# recepteur_led.net
KiCad netlist of a schematic drawn in EAGLE
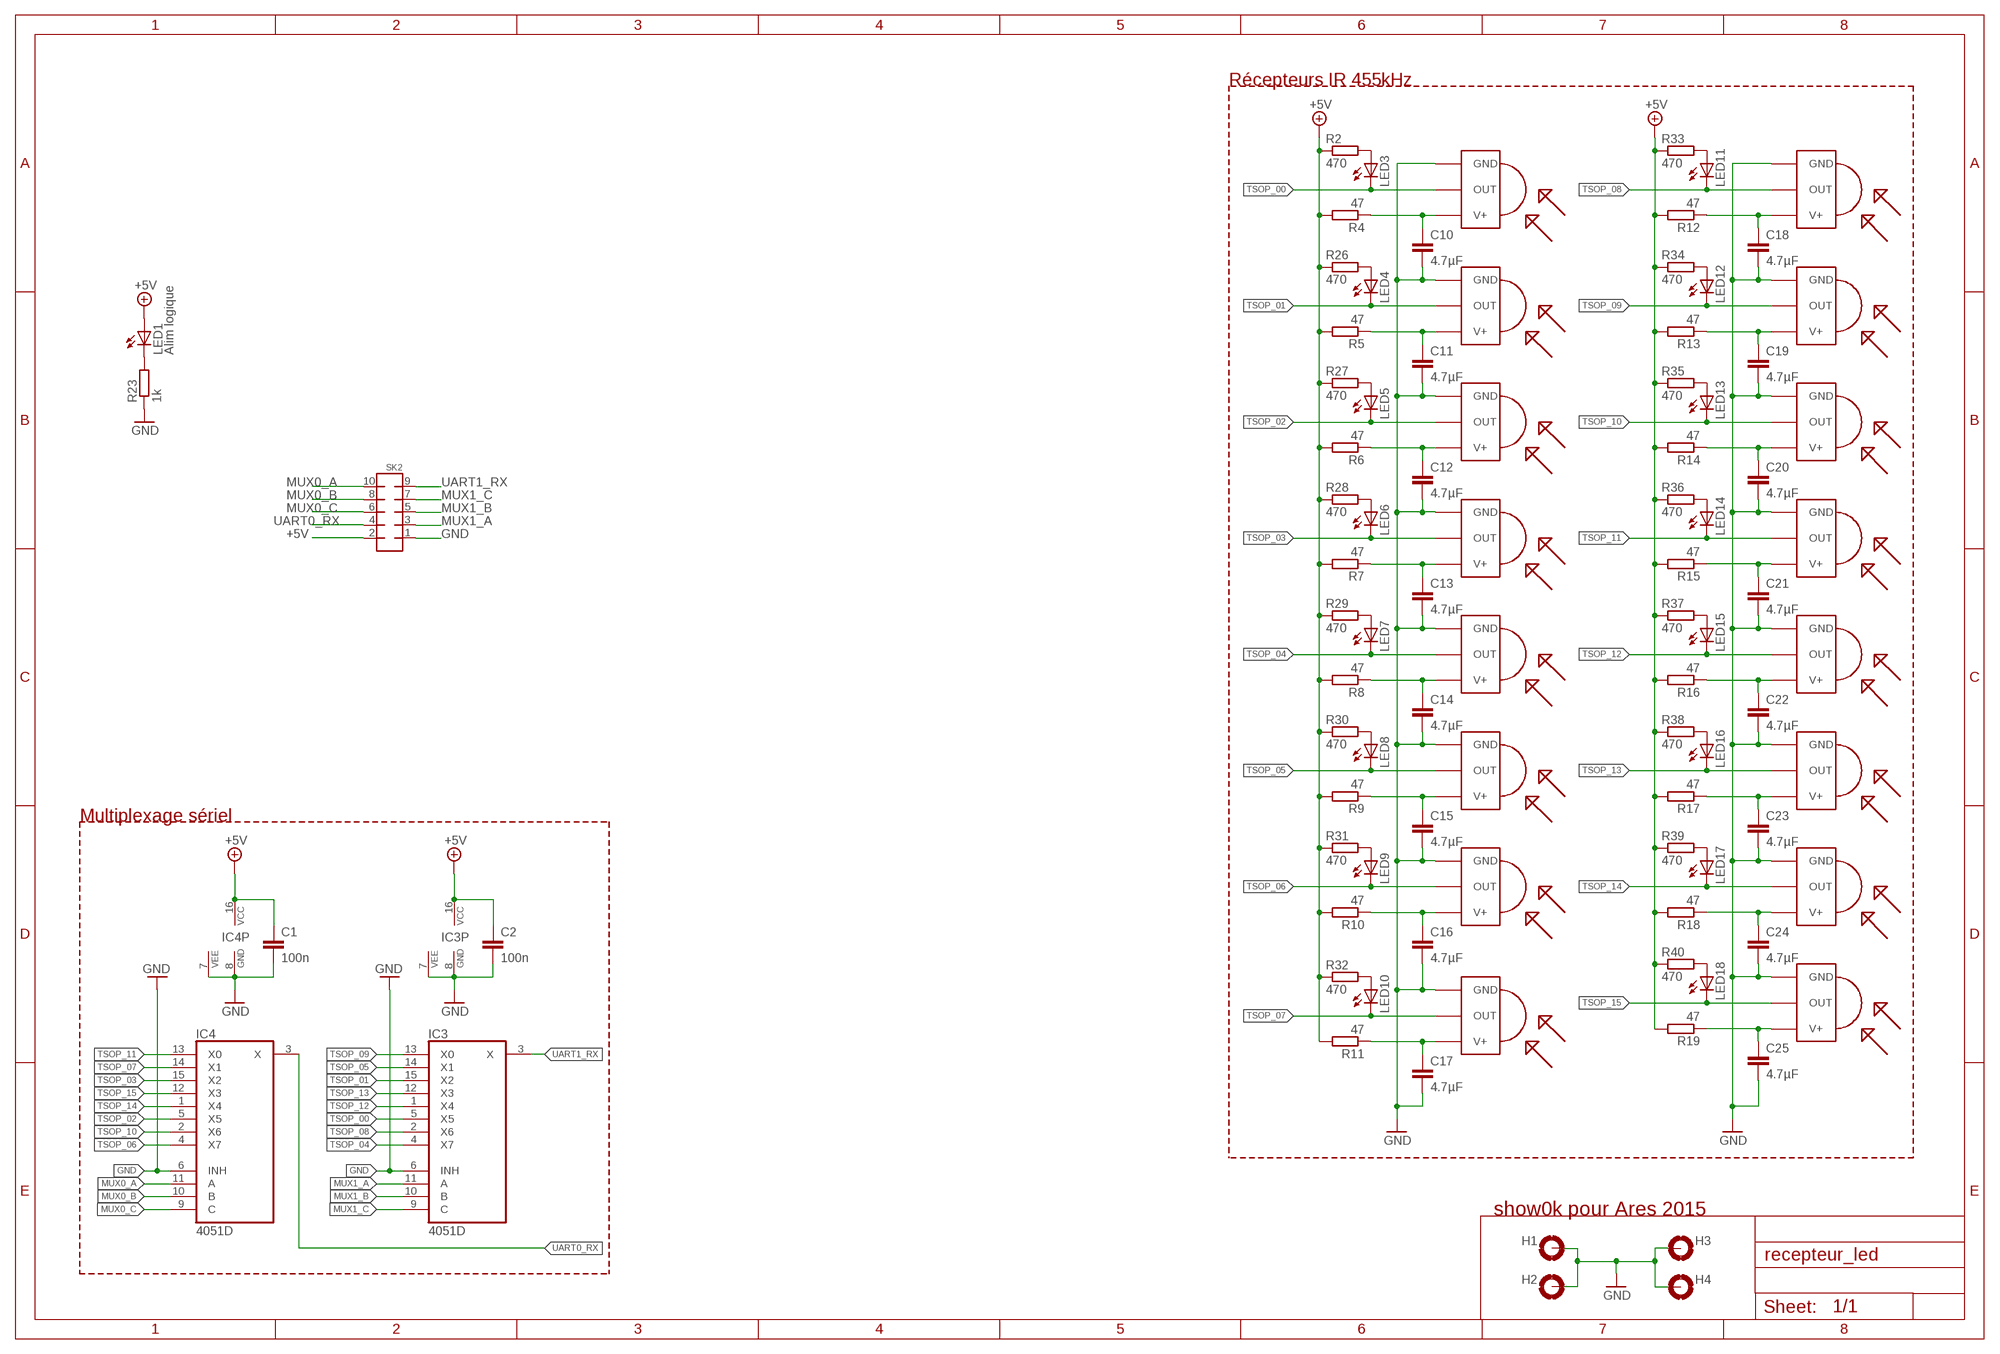
[diagram p0: schematic, sheet 1]

(export (version "E")
  (design (tool "Eeschema 10.0.6"))
  (components
    (comp (ref "C1")
      (value "100n")
      (footprint "eagle-import:C0805")
      (libsource (lib "eagle-import") (part "C-EUC0805"))
    )
    (comp (ref "C2")
      (value "100n")
      (footprint "eagle-import:C0805")
      (libsource (lib "eagle-import") (part "C-EUC0805"))
    )
    (comp (ref "C10")
      (value "4.7µF")
      (footprint "eagle-import:C0805")
      (libsource (lib "eagle-import") (part "C-EUC0805"))
    )
    (comp (ref "C11")
      (value "4.7µF")
      (footprint "eagle-import:C0805")
      (libsource (lib "eagle-import") (part "C-EUC0805"))
    )
    (comp (ref "C12")
      (value "4.7µF")
      (footprint "eagle-import:C0805")
      (libsource (lib "eagle-import") (part "C-EUC0805"))
    )
    (comp (ref "C13")
      (value "4.7µF")
      (footprint "eagle-import:C0805")
      (libsource (lib "eagle-import") (part "C-EUC0805"))
    )
    (comp (ref "C14")
      (value "4.7µF")
      (footprint "eagle-import:C0805")
      (libsource (lib "eagle-import") (part "C-EUC0805"))
    )
    (comp (ref "C15")
      (value "4.7µF")
      (footprint "eagle-import:C0805")
      (libsource (lib "eagle-import") (part "C-EUC0805"))
    )
    (comp (ref "C16")
      (value "4.7µF")
      (footprint "eagle-import:C0805")
      (libsource (lib "eagle-import") (part "C-EUC0805"))
    )
    (comp (ref "C17")
      (value "4.7µF")
      (footprint "eagle-import:C0805")
      (libsource (lib "eagle-import") (part "C-EUC0805"))
    )
    (comp (ref "C18")
      (value "4.7µF")
      (footprint "eagle-import:C0805")
      (libsource (lib "eagle-import") (part "C-EUC0805"))
    )
    (comp (ref "C19")
      (value "4.7µF")
      (footprint "eagle-import:C0805")
      (libsource (lib "eagle-import") (part "C-EUC0805"))
    )
    (comp (ref "C20")
      (value "4.7µF")
      (footprint "eagle-import:C0805")
      (libsource (lib "eagle-import") (part "C-EUC0805"))
    )
    (comp (ref "C21")
      (value "4.7µF")
      (footprint "eagle-import:C0805")
      (libsource (lib "eagle-import") (part "C-EUC0805"))
    )
    (comp (ref "C22")
      (value "4.7µF")
      (footprint "eagle-import:C0805")
      (libsource (lib "eagle-import") (part "C-EUC0805"))
    )
    (comp (ref "C23")
      (value "4.7µF")
      (footprint "eagle-import:C0805")
      (libsource (lib "eagle-import") (part "C-EUC0805"))
    )
    (comp (ref "C24")
      (value "4.7µF")
      (footprint "eagle-import:C0805")
      (libsource (lib "eagle-import") (part "C-EUC0805"))
    )
    (comp (ref "C25")
      (value "4.7µF")
      (footprint "eagle-import:C0805")
      (libsource (lib "eagle-import") (part "C-EUC0805"))
    )
    (comp (ref "H1")
      (value "MOUNT-PAD-ROUND3.0")
      (footprint "eagle-import:3,0-PAD")
      (libsource (lib "eagle-import") (part "MOUNT-PAD-ROUND3.0"))
    )
    (comp (ref "H2")
      (value "MOUNT-PAD-ROUND3.0")
      (footprint "eagle-import:3,0-PAD")
      (libsource (lib "eagle-import") (part "MOUNT-PAD-ROUND3.0"))
    )
    (comp (ref "H3")
      (value "MOUNT-PAD-ROUND3.0")
      (footprint "eagle-import:3,0-PAD")
      (libsource (lib "eagle-import") (part "MOUNT-PAD-ROUND3.0"))
    )
    (comp (ref "H4")
      (value "MOUNT-PAD-ROUND3.0")
      (footprint "eagle-import:3,0-PAD")
      (libsource (lib "eagle-import") (part "MOUNT-PAD-ROUND3.0"))
    )
    (comp (ref "IC3")
      (value "4051D")
      (footprint "eagle-import:SO16")
      (libsource (lib "eagle-import") (part "4051D"))
    )
    (comp (ref "IC4")
      (value "4051D")
      (footprint "eagle-import:SO16")
      (libsource (lib "eagle-import") (part "4051D"))
    )
    (comp (ref "LED1")
      (value "Alim logique")
      (footprint "eagle-import:CHIP-LED0805")
      (libsource (lib "eagle-import") (part "LEDCHIP-LED0805"))
    )
    (comp (ref "LED3")
      (value "LEDCHIP-LED0805")
      (footprint "eagle-import:CHIP-LED0805")
      (libsource (lib "eagle-import") (part "LEDCHIP-LED0805"))
    )
    (comp (ref "LED4")
      (value "LEDCHIP-LED0805")
      (footprint "eagle-import:CHIP-LED0805")
      (libsource (lib "eagle-import") (part "LEDCHIP-LED0805"))
    )
    (comp (ref "LED5")
      (value "LEDCHIP-LED0805")
      (footprint "eagle-import:CHIP-LED0805")
      (libsource (lib "eagle-import") (part "LEDCHIP-LED0805"))
    )
    (comp (ref "LED6")
      (value "LEDCHIP-LED0805")
      (footprint "eagle-import:CHIP-LED0805")
      (libsource (lib "eagle-import") (part "LEDCHIP-LED0805"))
    )
    (comp (ref "LED7")
      (value "LEDCHIP-LED0805")
      (footprint "eagle-import:CHIP-LED0805")
      (libsource (lib "eagle-import") (part "LEDCHIP-LED0805"))
    )
    (comp (ref "LED8")
      (value "LEDCHIP-LED0805")
      (footprint "eagle-import:CHIP-LED0805")
      (libsource (lib "eagle-import") (part "LEDCHIP-LED0805"))
    )
    (comp (ref "LED9")
      (value "LEDCHIP-LED0805")
      (footprint "eagle-import:CHIP-LED0805")
      (libsource (lib "eagle-import") (part "LEDCHIP-LED0805"))
    )
    (comp (ref "LED10")
      (value "LEDCHIP-LED0805")
      (footprint "eagle-import:CHIP-LED0805")
      (libsource (lib "eagle-import") (part "LEDCHIP-LED0805"))
    )
    (comp (ref "LED11")
      (value "LEDCHIP-LED0805")
      (footprint "eagle-import:CHIP-LED0805")
      (libsource (lib "eagle-import") (part "LEDCHIP-LED0805"))
    )
    (comp (ref "LED12")
      (value "LEDCHIP-LED0805")
      (footprint "eagle-import:CHIP-LED0805")
      (libsource (lib "eagle-import") (part "LEDCHIP-LED0805"))
    )
    (comp (ref "LED13")
      (value "LEDCHIP-LED0805")
      (footprint "eagle-import:CHIP-LED0805")
      (libsource (lib "eagle-import") (part "LEDCHIP-LED0805"))
    )
    (comp (ref "LED14")
      (value "LEDCHIP-LED0805")
      (footprint "eagle-import:CHIP-LED0805")
      (libsource (lib "eagle-import") (part "LEDCHIP-LED0805"))
    )
    (comp (ref "LED15")
      (value "LEDCHIP-LED0805")
      (footprint "eagle-import:CHIP-LED0805")
      (libsource (lib "eagle-import") (part "LEDCHIP-LED0805"))
    )
    (comp (ref "LED16")
      (value "LEDCHIP-LED0805")
      (footprint "eagle-import:CHIP-LED0805")
      (libsource (lib "eagle-import") (part "LEDCHIP-LED0805"))
    )
    (comp (ref "LED17")
      (value "LEDCHIP-LED0805")
      (footprint "eagle-import:CHIP-LED0805")
      (libsource (lib "eagle-import") (part "LEDCHIP-LED0805"))
    )
    (comp (ref "LED18")
      (value "LEDCHIP-LED0805")
      (footprint "eagle-import:CHIP-LED0805")
      (libsource (lib "eagle-import") (part "LEDCHIP-LED0805"))
    )
    (comp (ref "R2")
      (value "470")
      (footprint "eagle-import:R0805")
      (libsource (lib "eagle-import") (part "R-EU_R0805"))
    )
    (comp (ref "R4")
      (value "47")
      (footprint "eagle-import:R0805")
      (libsource (lib "eagle-import") (part "R-EU_R0805"))
    )
    (comp (ref "R5")
      (value "47")
      (footprint "eagle-import:R0805")
      (libsource (lib "eagle-import") (part "R-EU_R0805"))
    )
    (comp (ref "R6")
      (value "47")
      (footprint "eagle-import:R0805")
      (libsource (lib "eagle-import") (part "R-EU_R0805"))
    )
    (comp (ref "R7")
      (value "47")
      (footprint "eagle-import:R0805")
      (libsource (lib "eagle-import") (part "R-EU_R0805"))
    )
    (comp (ref "R8")
      (value "47")
      (footprint "eagle-import:R0805")
      (libsource (lib "eagle-import") (part "R-EU_R0805"))
    )
    (comp (ref "R9")
      (value "47")
      (footprint "eagle-import:R0805")
      (libsource (lib "eagle-import") (part "R-EU_R0805"))
    )
    (comp (ref "R10")
      (value "47")
      (footprint "eagle-import:R0805")
      (libsource (lib "eagle-import") (part "R-EU_R0805"))
    )
    (comp (ref "R11")
      (value "47")
      (footprint "eagle-import:R0805")
      (libsource (lib "eagle-import") (part "R-EU_R0805"))
    )
    (comp (ref "R12")
      (value "47")
      (footprint "eagle-import:R0805")
      (libsource (lib "eagle-import") (part "R-EU_R0805"))
    )
    (comp (ref "R13")
      (value "47")
      (footprint "eagle-import:R0805")
      (libsource (lib "eagle-import") (part "R-EU_R0805"))
    )
    (comp (ref "R14")
      (value "47")
      (footprint "eagle-import:R0805")
      (libsource (lib "eagle-import") (part "R-EU_R0805"))
    )
    (comp (ref "R15")
      (value "47")
      (footprint "eagle-import:R0805")
      (libsource (lib "eagle-import") (part "R-EU_R0805"))
    )
    (comp (ref "R16")
      (value "47")
      (footprint "eagle-import:R0805")
      (libsource (lib "eagle-import") (part "R-EU_R0805"))
    )
    (comp (ref "R17")
      (value "47")
      (footprint "eagle-import:R0805")
      (libsource (lib "eagle-import") (part "R-EU_R0805"))
    )
    (comp (ref "R18")
      (value "47")
      (footprint "eagle-import:R0805")
      (libsource (lib "eagle-import") (part "R-EU_R0805"))
    )
    (comp (ref "R19")
      (value "47")
      (footprint "eagle-import:R0805")
      (libsource (lib "eagle-import") (part "R-EU_R0805"))
    )
    (comp (ref "R23")
      (value "1k")
      (footprint "eagle-import:M0805")
      (libsource (lib "eagle-import") (part "R-EU_M0805"))
    )
    (comp (ref "R26")
      (value "470")
      (footprint "eagle-import:R0805")
      (libsource (lib "eagle-import") (part "R-EU_R0805"))
    )
    (comp (ref "R27")
      (value "470")
      (footprint "eagle-import:R0805")
      (libsource (lib "eagle-import") (part "R-EU_R0805"))
    )
    (comp (ref "R28")
      (value "470")
      (footprint "eagle-import:R0805")
      (libsource (lib "eagle-import") (part "R-EU_R0805"))
    )
    (comp (ref "R29")
      (value "470")
      (footprint "eagle-import:R0805")
      (libsource (lib "eagle-import") (part "R-EU_R0805"))
    )
    (comp (ref "R30")
      (value "470")
      (footprint "eagle-import:R0805")
      (libsource (lib "eagle-import") (part "R-EU_R0805"))
    )
    (comp (ref "R31")
      (value "470")
      (footprint "eagle-import:R0805")
      (libsource (lib "eagle-import") (part "R-EU_R0805"))
    )
    (comp (ref "R32")
      (value "470")
      (footprint "eagle-import:R0805")
      (libsource (lib "eagle-import") (part "R-EU_R0805"))
    )
    (comp (ref "R33")
      (value "470")
      (footprint "eagle-import:R0805")
      (libsource (lib "eagle-import") (part "R-EU_R0805"))
    )
    (comp (ref "R34")
      (value "470")
      (footprint "eagle-import:R0805")
      (libsource (lib "eagle-import") (part "R-EU_R0805"))
    )
    (comp (ref "R35")
      (value "470")
      (footprint "eagle-import:R0805")
      (libsource (lib "eagle-import") (part "R-EU_R0805"))
    )
    (comp (ref "R36")
      (value "470")
      (footprint "eagle-import:R0805")
      (libsource (lib "eagle-import") (part "R-EU_R0805"))
    )
    (comp (ref "R37")
      (value "470")
      (footprint "eagle-import:R0805")
      (libsource (lib "eagle-import") (part "R-EU_R0805"))
    )
    (comp (ref "R38")
      (value "470")
      (footprint "eagle-import:R0805")
      (libsource (lib "eagle-import") (part "R-EU_R0805"))
    )
    (comp (ref "R39")
      (value "470")
      (footprint "eagle-import:R0805")
      (libsource (lib "eagle-import") (part "R-EU_R0805"))
    )
    (comp (ref "R40")
      (value "470")
      (footprint "eagle-import:R0805")
      (libsource (lib "eagle-import") (part "R-EU_R0805"))
    )
    (comp (ref "SK2")
      (value "MMATCH-10-PTH")
      (footprint "eagle-import:AMP-215079-10")
      (libsource (lib "eagle-import") (part "MMATCH-10-PTH"))
    )
    (comp (ref "TSOP00")
      (value "TSOP7000")
      (footprint "eagle-import:TSOP18XX")
      (libsource (lib "eagle-import") (part "TSOP1830"))
    )
    (comp (ref "TSOP01")
      (value "TSOP7000")
      (footprint "eagle-import:TSOP18XX")
      (libsource (lib "eagle-import") (part "TSOP1830"))
    )
    (comp (ref "TSOP02")
      (value "TSOP7000")
      (footprint "eagle-import:TSOP18XX")
      (libsource (lib "eagle-import") (part "TSOP1830"))
    )
    (comp (ref "TSOP03")
      (value "TSOP7000")
      (footprint "eagle-import:TSOP18XX")
      (libsource (lib "eagle-import") (part "TSOP1830"))
    )
    (comp (ref "TSOP04")
      (value "TSOP7000")
      (footprint "eagle-import:TSOP18XX")
      (libsource (lib "eagle-import") (part "TSOP1830"))
    )
    (comp (ref "TSOP05")
      (value "TSOP7000")
      (footprint "eagle-import:TSOP18XX")
      (libsource (lib "eagle-import") (part "TSOP1830"))
    )
    (comp (ref "TSOP06")
      (value "TSOP7000")
      (footprint "eagle-import:TSOP18XX")
      (libsource (lib "eagle-import") (part "TSOP1830"))
    )
    (comp (ref "TSOP07")
      (value "TSOP7000")
      (footprint "eagle-import:TSOP18XX")
      (libsource (lib "eagle-import") (part "TSOP1830"))
    )
    (comp (ref "TSOP08")
      (value "TSOP7000")
      (footprint "eagle-import:TSOP18XX")
      (libsource (lib "eagle-import") (part "TSOP1830"))
    )
    (comp (ref "TSOP09")
      (value "TSOP7000")
      (footprint "eagle-import:TSOP18XX")
      (libsource (lib "eagle-import") (part "TSOP1830"))
    )
    (comp (ref "TSOP10")
      (value "TSOP7000")
      (footprint "eagle-import:TSOP18XX")
      (libsource (lib "eagle-import") (part "TSOP1830"))
    )
    (comp (ref "TSOP11")
      (value "TSOP7000")
      (footprint "eagle-import:TSOP18XX")
      (libsource (lib "eagle-import") (part "TSOP1830"))
    )
    (comp (ref "TSOP12")
      (value "TSOP7000")
      (footprint "eagle-import:TSOP18XX")
      (libsource (lib "eagle-import") (part "TSOP1830"))
    )
    (comp (ref "TSOP13")
      (value "TSOP7000")
      (footprint "eagle-import:TSOP18XX")
      (libsource (lib "eagle-import") (part "TSOP1830"))
    )
    (comp (ref "TSOP14")
      (value "TSOP7000")
      (footprint "eagle-import:TSOP18XX")
      (libsource (lib "eagle-import") (part "TSOP1830"))
    )
    (comp (ref "TSOP15")
      (value "TSOP7000")
      (footprint "eagle-import:TSOP18XX")
      (libsource (lib "eagle-import") (part "TSOP1830"))
    )
  )
  (nets
    (net (code "1") (name "+5V") (class "Default")
      (node (ref "C1") (pin "1") (pinfunction "1_1") (pintype "passive"))
      (node (ref "C2") (pin "1") (pinfunction "1_1") (pintype "passive"))
      (node (ref "IC3") (pin "16") (pinfunction "VCC_16") (pintype "power_in"))
      (node (ref "IC4") (pin "16") (pinfunction "VCC_16") (pintype "power_in"))
      (node (ref "LED1") (pin "A") (pinfunction "A_A") (pintype "passive"))
      (node (ref "R10") (pin "2") (pinfunction "2_2") (pintype "passive"))
      (node (ref "R11") (pin "2") (pinfunction "2_2") (pintype "passive"))
      (node (ref "R12") (pin "2") (pinfunction "2_2") (pintype "passive"))
      (node (ref "R13") (pin "2") (pinfunction "2_2") (pintype "passive"))
      (node (ref "R14") (pin "2") (pinfunction "2_2") (pintype "passive"))
      (node (ref "R15") (pin "2") (pinfunction "2_2") (pintype "passive"))
      (node (ref "R16") (pin "2") (pinfunction "2_2") (pintype "passive"))
      (node (ref "R17") (pin "2") (pinfunction "2_2") (pintype "passive"))
      (node (ref "R18") (pin "2") (pinfunction "2_2") (pintype "passive"))
      (node (ref "R19") (pin "2") (pinfunction "2_2") (pintype "passive"))
      (node (ref "R2") (pin "1") (pinfunction "1_1") (pintype "passive"))
      (node (ref "R26") (pin "1") (pinfunction "1_1") (pintype "passive"))
      (node (ref "R27") (pin "1") (pinfunction "1_1") (pintype "passive"))
      (node (ref "R28") (pin "1") (pinfunction "1_1") (pintype "passive"))
      (node (ref "R29") (pin "1") (pinfunction "1_1") (pintype "passive"))
      (node (ref "R30") (pin "1") (pinfunction "1_1") (pintype "passive"))
      (node (ref "R31") (pin "1") (pinfunction "1_1") (pintype "passive"))
      (node (ref "R32") (pin "1") (pinfunction "1_1") (pintype "passive"))
      (node (ref "R33") (pin "1") (pinfunction "1_1") (pintype "passive"))
      (node (ref "R34") (pin "1") (pinfunction "1_1") (pintype "passive"))
      (node (ref "R35") (pin "1") (pinfunction "1_1") (pintype "passive"))
      (node (ref "R36") (pin "1") (pinfunction "1_1") (pintype "passive"))
      (node (ref "R37") (pin "1") (pinfunction "1_1") (pintype "passive"))
      (node (ref "R38") (pin "1") (pinfunction "1_1") (pintype "passive"))
      (node (ref "R39") (pin "1") (pinfunction "1_1") (pintype "passive"))
      (node (ref "R4") (pin "2") (pinfunction "2_2") (pintype "passive"))
      (node (ref "R40") (pin "1") (pinfunction "1_1") (pintype "passive"))
      (node (ref "R5") (pin "2") (pinfunction "2_2") (pintype "passive"))
      (node (ref "R6") (pin "2") (pinfunction "2_2") (pintype "passive"))
      (node (ref "R7") (pin "2") (pinfunction "2_2") (pintype "passive"))
      (node (ref "R8") (pin "2") (pinfunction "2_2") (pintype "passive"))
      (node (ref "R9") (pin "2") (pinfunction "2_2") (pintype "passive"))
      (node (ref "SK2") (pin "2") (pinfunction "2_2") (pintype "bidirectional"))
    )
    (net (code "2") (name "GND") (class "Default")
      (node (ref "C1") (pin "2") (pinfunction "2_2") (pintype "passive"))
      (node (ref "C10") (pin "2") (pinfunction "2_2") (pintype "passive"))
      (node (ref "C11") (pin "2") (pinfunction "2_2") (pintype "passive"))
      (node (ref "C12") (pin "2") (pinfunction "2_2") (pintype "passive"))
      (node (ref "C13") (pin "2") (pinfunction "2_2") (pintype "passive"))
      (node (ref "C14") (pin "2") (pinfunction "2_2") (pintype "passive"))
      (node (ref "C15") (pin "2") (pinfunction "2_2") (pintype "passive"))
      (node (ref "C16") (pin "2") (pinfunction "2_2") (pintype "passive"))
      (node (ref "C17") (pin "2") (pinfunction "2_2") (pintype "passive"))
      (node (ref "C18") (pin "2") (pinfunction "2_2") (pintype "passive"))
      (node (ref "C19") (pin "2") (pinfunction "2_2") (pintype "passive"))
      (node (ref "C2") (pin "2") (pinfunction "2_2") (pintype "passive"))
      (node (ref "C20") (pin "2") (pinfunction "2_2") (pintype "passive"))
      (node (ref "C21") (pin "2") (pinfunction "2_2") (pintype "passive"))
      (node (ref "C22") (pin "2") (pinfunction "2_2") (pintype "passive"))
      (node (ref "C23") (pin "2") (pinfunction "2_2") (pintype "passive"))
      (node (ref "C24") (pin "2") (pinfunction "2_2") (pintype "passive"))
      (node (ref "C25") (pin "2") (pinfunction "2_2") (pintype "passive"))
      (node (ref "H1") (pin "B3,0") (pinfunction "MOUNT_B3,0") (pintype "passive"))
      (node (ref "H2") (pin "B3,0") (pinfunction "MOUNT_B3,0") (pintype "passive"))
      (node (ref "H3") (pin "B3,0") (pinfunction "MOUNT_B3,0") (pintype "passive"))
      (node (ref "H4") (pin "B3,0") (pinfunction "MOUNT_B3,0") (pintype "passive"))
      (node (ref "IC3") (pin "6") (pinfunction "INH_6") (pintype "input"))
      (node (ref "IC3") (pin "7") (pinfunction "VEE_7") (pintype "power_in"))
      (node (ref "IC3") (pin "8") (pinfunction "GND_8") (pintype "power_in"))
      (node (ref "IC4") (pin "6") (pinfunction "INH_6") (pintype "input"))
      (node (ref "IC4") (pin "7") (pinfunction "VEE_7") (pintype "power_in"))
      (node (ref "IC4") (pin "8") (pinfunction "GND_8") (pintype "power_in"))
      (node (ref "R23") (pin "1") (pinfunction "1_1") (pintype "passive"))
      (node (ref "SK2") (pin "1") (pinfunction "1_1") (pintype "bidirectional"))
      (node (ref "TSOP00") (pin "GND") (pinfunction "GND_GND") (pintype "bidirectional"))
      (node (ref "TSOP01") (pin "GND") (pinfunction "GND_GND") (pintype "bidirectional"))
      (node (ref "TSOP02") (pin "GND") (pinfunction "GND_GND") (pintype "bidirectional"))
      (node (ref "TSOP03") (pin "GND") (pinfunction "GND_GND") (pintype "bidirectional"))
      (node (ref "TSOP04") (pin "GND") (pinfunction "GND_GND") (pintype "bidirectional"))
      (node (ref "TSOP05") (pin "GND") (pinfunction "GND_GND") (pintype "bidirectional"))
      (node (ref "TSOP06") (pin "GND") (pinfunction "GND_GND") (pintype "bidirectional"))
      (node (ref "TSOP07") (pin "GND") (pinfunction "GND_GND") (pintype "bidirectional"))
      (node (ref "TSOP08") (pin "GND") (pinfunction "GND_GND") (pintype "bidirectional"))
      (node (ref "TSOP09") (pin "GND") (pinfunction "GND_GND") (pintype "bidirectional"))
      (node (ref "TSOP10") (pin "GND") (pinfunction "GND_GND") (pintype "bidirectional"))
      (node (ref "TSOP11") (pin "GND") (pinfunction "GND_GND") (pintype "bidirectional"))
      (node (ref "TSOP12") (pin "GND") (pinfunction "GND_GND") (pintype "bidirectional"))
      (node (ref "TSOP13") (pin "GND") (pinfunction "GND_GND") (pintype "bidirectional"))
      (node (ref "TSOP14") (pin "GND") (pinfunction "GND_GND") (pintype "bidirectional"))
      (node (ref "TSOP15") (pin "GND") (pinfunction "GND_GND") (pintype "bidirectional"))
    )
    (net (code "3") (name "MUX0_A") (class "Default")
      (node (ref "IC4") (pin "11") (pinfunction "A_11") (pintype "input"))
      (node (ref "SK2") (pin "10") (pinfunction "10_10") (pintype "bidirectional"))
    )
    (net (code "4") (name "MUX0_B") (class "Default")
      (node (ref "IC4") (pin "10") (pinfunction "B_10") (pintype "input"))
      (node (ref "SK2") (pin "8") (pinfunction "8_8") (pintype "bidirectional"))
    )
    (net (code "5") (name "MUX0_C") (class "Default")
      (node (ref "IC4") (pin "9") (pinfunction "C_9") (pintype "input"))
      (node (ref "SK2") (pin "6") (pinfunction "6_6") (pintype "bidirectional"))
    )
    (net (code "6") (name "MUX1_A") (class "Default")
      (node (ref "IC3") (pin "11") (pinfunction "A_11") (pintype "input"))
      (node (ref "SK2") (pin "3") (pinfunction "3_3") (pintype "bidirectional"))
    )
    (net (code "7") (name "MUX1_B") (class "Default")
      (node (ref "IC3") (pin "10") (pinfunction "B_10") (pintype "input"))
      (node (ref "SK2") (pin "5") (pinfunction "5_5") (pintype "bidirectional"))
    )
    (net (code "8") (name "MUX1_C") (class "Default")
      (node (ref "IC3") (pin "9") (pinfunction "C_9") (pintype "input"))
      (node (ref "SK2") (pin "7") (pinfunction "7_7") (pintype "bidirectional"))
    )
    (net (code "9") (name "Net-(LED1-PadC)") (class "Default")
      (node (ref "LED1") (pin "C") (pinfunction "C_C") (pintype "passive"))
      (node (ref "R23") (pin "2") (pinfunction "2_2") (pintype "passive"))
    )
    (net (code "10") (name "Net-(LED3-PadA)") (class "Default")
      (node (ref "LED3") (pin "A") (pinfunction "A_A") (pintype "passive"))
      (node (ref "R2") (pin "2") (pinfunction "2_2") (pintype "passive"))
    )
    (net (code "11") (name "Net-(LED4-PadA)") (class "Default")
      (node (ref "LED4") (pin "A") (pinfunction "A_A") (pintype "passive"))
      (node (ref "R26") (pin "2") (pinfunction "2_2") (pintype "passive"))
    )
    (net (code "12") (name "Net-(LED5-PadA)") (class "Default")
      (node (ref "LED5") (pin "A") (pinfunction "A_A") (pintype "passive"))
      (node (ref "R27") (pin "2") (pinfunction "2_2") (pintype "passive"))
    )
    (net (code "13") (name "Net-(LED6-PadA)") (class "Default")
      (node (ref "LED6") (pin "A") (pinfunction "A_A") (pintype "passive"))
      (node (ref "R28") (pin "2") (pinfunction "2_2") (pintype "passive"))
    )
    (net (code "14") (name "Net-(LED7-PadA)") (class "Default")
      (node (ref "LED7") (pin "A") (pinfunction "A_A") (pintype "passive"))
      (node (ref "R29") (pin "2") (pinfunction "2_2") (pintype "passive"))
    )
    (net (code "15") (name "Net-(LED8-PadA)") (class "Default")
      (node (ref "LED8") (pin "A") (pinfunction "A_A") (pintype "passive"))
      (node (ref "R30") (pin "2") (pinfunction "2_2") (pintype "passive"))
    )
    (net (code "16") (name "Net-(LED9-PadA)") (class "Default")
      (node (ref "LED9") (pin "A") (pinfunction "A_A") (pintype "passive"))
      (node (ref "R31") (pin "2") (pinfunction "2_2") (pintype "passive"))
    )
    (net (code "17") (name "Net-(LED10-PadA)") (class "Default")
      (node (ref "LED10") (pin "A") (pinfunction "A_A") (pintype "passive"))
      (node (ref "R32") (pin "2") (pinfunction "2_2") (pintype "passive"))
    )
    (net (code "18") (name "Net-(LED11-PadA)") (class "Default")
      (node (ref "LED11") (pin "A") (pinfunction "A_A") (pintype "passive"))
      (node (ref "R33") (pin "2") (pinfunction "2_2") (pintype "passive"))
    )
    (net (code "19") (name "Net-(LED12-PadA)") (class "Default")
      (node (ref "LED12") (pin "A") (pinfunction "A_A") (pintype "passive"))
      (node (ref "R34") (pin "2") (pinfunction "2_2") (pintype "passive"))
    )
    (net (code "20") (name "Net-(LED13-PadA)") (class "Default")
      (node (ref "LED13") (pin "A") (pinfunction "A_A") (pintype "passive"))
      (node (ref "R35") (pin "2") (pinfunction "2_2") (pintype "passive"))
    )
    (net (code "21") (name "Net-(LED14-PadA)") (class "Default")
      (node (ref "LED14") (pin "A") (pinfunction "A_A") (pintype "passive"))
      (node (ref "R36") (pin "2") (pinfunction "2_2") (pintype "passive"))
    )
    (net (code "22") (name "Net-(LED15-PadA)") (class "Default")
      (node (ref "LED15") (pin "A") (pinfunction "A_A") (pintype "passive"))
      (node (ref "R37") (pin "2") (pinfunction "2_2") (pintype "passive"))
    )
    (net (code "23") (name "Net-(LED16-PadA)") (class "Default")
      (node (ref "LED16") (pin "A") (pinfunction "A_A") (pintype "passive"))
      (node (ref "R38") (pin "2") (pinfunction "2_2") (pintype "passive"))
    )
    (net (code "24") (name "Net-(LED17-PadA)") (class "Default")
      (node (ref "LED17") (pin "A") (pinfunction "A_A") (pintype "passive"))
      (node (ref "R39") (pin "2") (pinfunction "2_2") (pintype "passive"))
    )
    (net (code "25") (name "Net-(LED18-PadA)") (class "Default")
      (node (ref "LED18") (pin "A") (pinfunction "A_A") (pintype "passive"))
      (node (ref "R40") (pin "2") (pinfunction "2_2") (pintype "passive"))
    )
    (net (code "26") (name "Net-(TSOP00-V+)") (class "Default")
      (node (ref "C10") (pin "1") (pinfunction "1_1") (pintype "passive"))
      (node (ref "R4") (pin "1") (pinfunction "1_1") (pintype "passive"))
      (node (ref "TSOP00") (pin "VCC") (pinfunction "V+_VCC") (pintype "bidirectional"))
    )
    (net (code "27") (name "Net-(TSOP01-V+)") (class "Default")
      (node (ref "C11") (pin "1") (pinfunction "1_1") (pintype "passive"))
      (node (ref "R5") (pin "1") (pinfunction "1_1") (pintype "passive"))
      (node (ref "TSOP01") (pin "VCC") (pinfunction "V+_VCC") (pintype "bidirectional"))
    )
    (net (code "28") (name "Net-(TSOP02-V+)") (class "Default")
      (node (ref "C12") (pin "1") (pinfunction "1_1") (pintype "passive"))
      (node (ref "R6") (pin "1") (pinfunction "1_1") (pintype "passive"))
      (node (ref "TSOP02") (pin "VCC") (pinfunction "V+_VCC") (pintype "bidirectional"))
    )
    (net (code "29") (name "Net-(TSOP03-V+)") (class "Default")
      (node (ref "C13") (pin "1") (pinfunction "1_1") (pintype "passive"))
      (node (ref "R7") (pin "1") (pinfunction "1_1") (pintype "passive"))
      (node (ref "TSOP03") (pin "VCC") (pinfunction "V+_VCC") (pintype "bidirectional"))
    )
    (net (code "30") (name "Net-(TSOP04-V+)") (class "Default")
      (node (ref "C14") (pin "1") (pinfunction "1_1") (pintype "passive"))
      (node (ref "R8") (pin "1") (pinfunction "1_1") (pintype "passive"))
      (node (ref "TSOP04") (pin "VCC") (pinfunction "V+_VCC") (pintype "bidirectional"))
    )
    (net (code "31") (name "Net-(TSOP05-V+)") (class "Default")
      (node (ref "C15") (pin "1") (pinfunction "1_1") (pintype "passive"))
      (node (ref "R9") (pin "1") (pinfunction "1_1") (pintype "passive"))
      (node (ref "TSOP05") (pin "VCC") (pinfunction "V+_VCC") (pintype "bidirectional"))
    )
    (net (code "32") (name "Net-(TSOP06-V+)") (class "Default")
      (node (ref "C16") (pin "1") (pinfunction "1_1") (pintype "passive"))
      (node (ref "R10") (pin "1") (pinfunction "1_1") (pintype "passive"))
      (node (ref "TSOP06") (pin "VCC") (pinfunction "V+_VCC") (pintype "bidirectional"))
    )
    (net (code "33") (name "Net-(TSOP07-V+)") (class "Default")
      (node (ref "C17") (pin "1") (pinfunction "1_1") (pintype "passive"))
      (node (ref "R11") (pin "1") (pinfunction "1_1") (pintype "passive"))
      (node (ref "TSOP07") (pin "VCC") (pinfunction "V+_VCC") (pintype "bidirectional"))
    )
    (net (code "34") (name "Net-(TSOP08-V+)") (class "Default")
      (node (ref "C18") (pin "1") (pinfunction "1_1") (pintype "passive"))
      (node (ref "R12") (pin "1") (pinfunction "1_1") (pintype "passive"))
      (node (ref "TSOP08") (pin "VCC") (pinfunction "V+_VCC") (pintype "bidirectional"))
    )
    (net (code "35") (name "Net-(TSOP09-V+)") (class "Default")
      (node (ref "C19") (pin "1") (pinfunction "1_1") (pintype "passive"))
      (node (ref "R13") (pin "1") (pinfunction "1_1") (pintype "passive"))
      (node (ref "TSOP09") (pin "VCC") (pinfunction "V+_VCC") (pintype "bidirectional"))
    )
    (net (code "36") (name "Net-(TSOP10-V+)") (class "Default")
      (node (ref "C20") (pin "1") (pinfunction "1_1") (pintype "passive"))
      (node (ref "R14") (pin "1") (pinfunction "1_1") (pintype "passive"))
      (node (ref "TSOP10") (pin "VCC") (pinfunction "V+_VCC") (pintype "bidirectional"))
    )
    (net (code "37") (name "Net-(TSOP11-V+)") (class "Default")
      (node (ref "C21") (pin "1") (pinfunction "1_1") (pintype "passive"))
      (node (ref "R15") (pin "1") (pinfunction "1_1") (pintype "passive"))
      (node (ref "TSOP11") (pin "VCC") (pinfunction "V+_VCC") (pintype "bidirectional"))
    )
    (net (code "38") (name "Net-(TSOP12-V+)") (class "Default")
      (node (ref "C22") (pin "1") (pinfunction "1_1") (pintype "passive"))
      (node (ref "R16") (pin "1") (pinfunction "1_1") (pintype "passive"))
      (node (ref "TSOP12") (pin "VCC") (pinfunction "V+_VCC") (pintype "bidirectional"))
    )
    (net (code "39") (name "Net-(TSOP13-V+)") (class "Default")
      (node (ref "C23") (pin "1") (pinfunction "1_1") (pintype "passive"))
      (node (ref "R17") (pin "1") (pinfunction "1_1") (pintype "passive"))
      (node (ref "TSOP13") (pin "VCC") (pinfunction "V+_VCC") (pintype "bidirectional"))
    )
    (net (code "40") (name "Net-(TSOP14-V+)") (class "Default")
      (node (ref "C24") (pin "1") (pinfunction "1_1") (pintype "passive"))
      (node (ref "R18") (pin "1") (pinfunction "1_1") (pintype "passive"))
      (node (ref "TSOP14") (pin "VCC") (pinfunction "V+_VCC") (pintype "bidirectional"))
    )
    (net (code "41") (name "Net-(TSOP15-V+)") (class "Default")
      (node (ref "C25") (pin "1") (pinfunction "1_1") (pintype "passive"))
      (node (ref "R19") (pin "1") (pinfunction "1_1") (pintype "passive"))
      (node (ref "TSOP15") (pin "VCC") (pinfunction "V+_VCC") (pintype "bidirectional"))
    )
    (net (code "42") (name "TSOP_00") (class "Default")
      (node (ref "IC3") (pin "5") (pinfunction "X5_5") (pintype "bidirectional"))
      (node (ref "LED3") (pin "C") (pinfunction "C_C") (pintype "passive"))
      (node (ref "TSOP00") (pin "OUT") (pinfunction "OUT_OUT") (pintype "bidirectional"))
    )
    (net (code "43") (name "TSOP_01") (class "Default")
      (node (ref "IC3") (pin "15") (pinfunction "X2_15") (pintype "bidirectional"))
      (node (ref "LED4") (pin "C") (pinfunction "C_C") (pintype "passive"))
      (node (ref "TSOP01") (pin "OUT") (pinfunction "OUT_OUT") (pintype "bidirectional"))
    )
    (net (code "44") (name "TSOP_02") (class "Default")
      (node (ref "IC4") (pin "5") (pinfunction "X5_5") (pintype "bidirectional"))
      (node (ref "LED5") (pin "C") (pinfunction "C_C") (pintype "passive"))
      (node (ref "TSOP02") (pin "OUT") (pinfunction "OUT_OUT") (pintype "bidirectional"))
    )
    (net (code "45") (name "TSOP_03") (class "Default")
      (node (ref "IC4") (pin "15") (pinfunction "X2_15") (pintype "bidirectional"))
      (node (ref "LED6") (pin "C") (pinfunction "C_C") (pintype "passive"))
      (node (ref "TSOP03") (pin "OUT") (pinfunction "OUT_OUT") (pintype "bidirectional"))
    )
    (net (code "46") (name "TSOP_04") (class "Default")
      (node (ref "IC3") (pin "4") (pinfunction "X7_4") (pintype "bidirectional"))
      (node (ref "LED7") (pin "C") (pinfunction "C_C") (pintype "passive"))
      (node (ref "TSOP04") (pin "OUT") (pinfunction "OUT_OUT") (pintype "bidirectional"))
    )
    (net (code "47") (name "TSOP_05") (class "Default")
      (node (ref "IC3") (pin "14") (pinfunction "X1_14") (pintype "bidirectional"))
      (node (ref "LED8") (pin "C") (pinfunction "C_C") (pintype "passive"))
      (node (ref "TSOP05") (pin "OUT") (pinfunction "OUT_OUT") (pintype "bidirectional"))
    )
    (net (code "48") (name "TSOP_06") (class "Default")
      (node (ref "IC4") (pin "4") (pinfunction "X7_4") (pintype "bidirectional"))
      (node (ref "LED9") (pin "C") (pinfunction "C_C") (pintype "passive"))
      (node (ref "TSOP06") (pin "OUT") (pinfunction "OUT_OUT") (pintype "bidirectional"))
    )
    (net (code "49") (name "TSOP_07") (class "Default")
      (node (ref "IC4") (pin "14") (pinfunction "X1_14") (pintype "bidirectional"))
      (node (ref "LED10") (pin "C") (pinfunction "C_C") (pintype "passive"))
      (node (ref "TSOP07") (pin "OUT") (pinfunction "OUT_OUT") (pintype "bidirectional"))
    )
    (net (code "50") (name "TSOP_08") (class "Default")
      (node (ref "IC3") (pin "2") (pinfunction "X6_2") (pintype "bidirectional"))
      (node (ref "LED11") (pin "C") (pinfunction "C_C") (pintype "passive"))
      (node (ref "TSOP08") (pin "OUT") (pinfunction "OUT_OUT") (pintype "bidirectional"))
    )
    (net (code "51") (name "TSOP_09") (class "Default")
      (node (ref "IC3") (pin "13") (pinfunction "X0_13") (pintype "bidirectional"))
      (node (ref "LED12") (pin "C") (pinfunction "C_C") (pintype "passive"))
      (node (ref "TSOP09") (pin "OUT") (pinfunction "OUT_OUT") (pintype "bidirectional"))
    )
    (net (code "52") (name "TSOP_10") (class "Default")
      (node (ref "IC4") (pin "2") (pinfunction "X6_2") (pintype "bidirectional"))
      (node (ref "LED13") (pin "C") (pinfunction "C_C") (pintype "passive"))
      (node (ref "TSOP10") (pin "OUT") (pinfunction "OUT_OUT") (pintype "bidirectional"))
    )
    (net (code "53") (name "TSOP_11") (class "Default")
      (node (ref "IC4") (pin "13") (pinfunction "X0_13") (pintype "bidirectional"))
      (node (ref "LED14") (pin "C") (pinfunction "C_C") (pintype "passive"))
      (node (ref "TSOP11") (pin "OUT") (pinfunction "OUT_OUT") (pintype "bidirectional"))
    )
    (net (code "54") (name "TSOP_12") (class "Default")
      (node (ref "IC3") (pin "1") (pinfunction "X4_1") (pintype "bidirectional"))
      (node (ref "LED15") (pin "C") (pinfunction "C_C") (pintype "passive"))
      (node (ref "TSOP12") (pin "OUT") (pinfunction "OUT_OUT") (pintype "bidirectional"))
    )
    (net (code "55") (name "TSOP_13") (class "Default")
      (node (ref "IC3") (pin "12") (pinfunction "X3_12") (pintype "bidirectional"))
      (node (ref "LED16") (pin "C") (pinfunction "C_C") (pintype "passive"))
      (node (ref "TSOP13") (pin "OUT") (pinfunction "OUT_OUT") (pintype "bidirectional"))
    )
    (net (code "56") (name "TSOP_14") (class "Default")
      (node (ref "IC4") (pin "1") (pinfunction "X4_1") (pintype "bidirectional"))
      (node (ref "LED17") (pin "C") (pinfunction "C_C") (pintype "passive"))
      (node (ref "TSOP14") (pin "OUT") (pinfunction "OUT_OUT") (pintype "bidirectional"))
    )
    (net (code "57") (name "TSOP_15") (class "Default")
      (node (ref "IC4") (pin "12") (pinfunction "X3_12") (pintype "bidirectional"))
      (node (ref "LED18") (pin "C") (pinfunction "C_C") (pintype "passive"))
      (node (ref "TSOP15") (pin "OUT") (pinfunction "OUT_OUT") (pintype "bidirectional"))
    )
    (net (code "58") (name "UART0_RX") (class "Default")
      (node (ref "IC4") (pin "3") (pinfunction "X_3") (pintype "bidirectional"))
      (node (ref "SK2") (pin "4") (pinfunction "4_4") (pintype "bidirectional"))
    )
    (net (code "59") (name "UART1_RX") (class "Default")
      (node (ref "IC3") (pin "3") (pinfunction "X_3") (pintype "bidirectional"))
      (node (ref "SK2") (pin "9") (pinfunction "9_9") (pintype "bidirectional"))
    )
  )
)
